# HILOW_Drivers.net
KiCad netlist of a schematic drawn in EasyEDA Pro
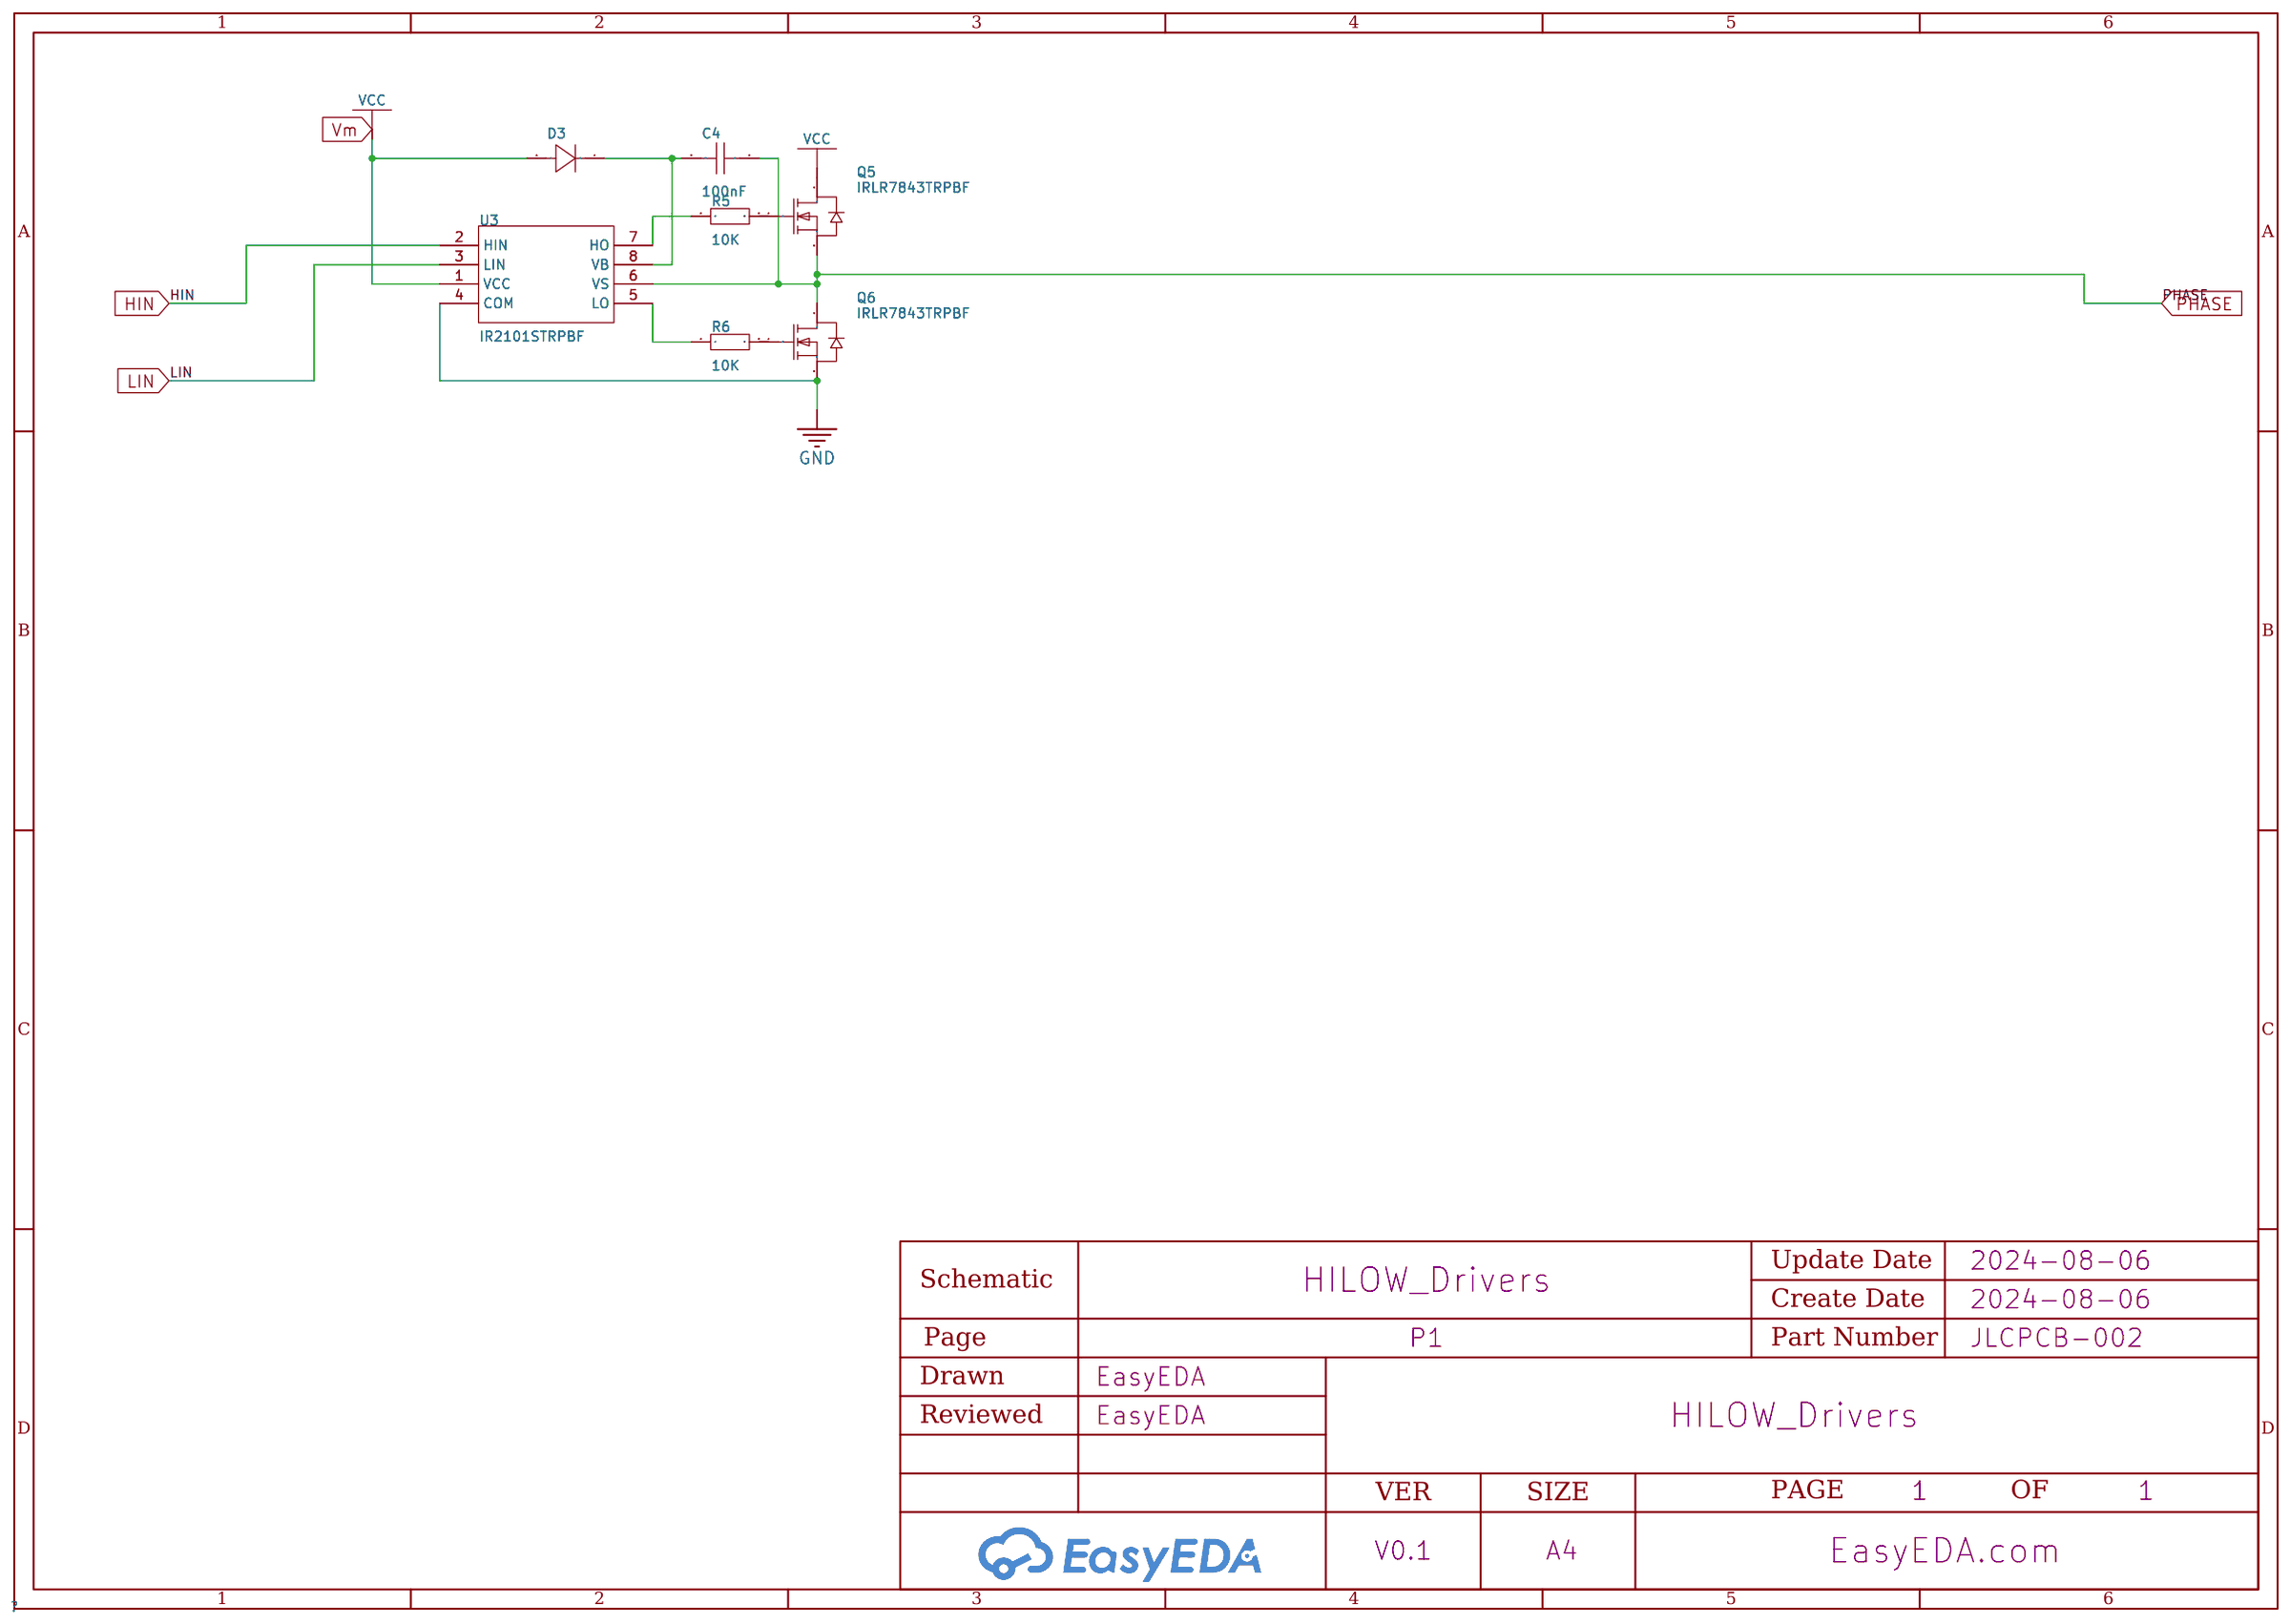
[diagram p0: schematic sheet]

(export (version "E")
  (design (tool "Eeschema 10.0.6"))
  (components
    (comp (ref "C4")
      (value "100nF")
      (footprint "easyedapro:C0603")
      (libsource (lib "easyedapro") (part "CAP"))
    )
    (comp (ref "D3")
      (value "~")
      (footprint "easyedapro:DO-41_BD2.4-L4.7-P8.70-D0.9-RD")
      (libsource (lib "easyedapro") (part "D_1N4007"))
    )
    (comp (ref "Q5")
      (value "IRLR7843TRPBF")
      (footprint "easyedapro:TO-252-2_L6.5-W6.1-P4.58-LS10.0-TR")
      (fields (field (name "Manufacturer") "Infineon(英飞凌)"))
      (libsource (lib "easyedapro") (part "IRLR7843TRPBF"))
    )
    (comp (ref "Q6")
      (value "IRLR7843TRPBF")
      (footprint "easyedapro:TO-252-2_L6.5-W6.1-P4.58-LS10.0-TR")
      (fields (field (name "Manufacturer") "Infineon(英飞凌)"))
      (libsource (lib "easyedapro") (part "IRLR7843TRPBF"))
    )
    (comp (ref "R5") (value "10K") (footprint "easyedapro:R0603") (libsource (lib "easyedapro") (part "Res")))
    (comp (ref "R6") (value "10K") (footprint "easyedapro:R0603") (libsource (lib "easyedapro") (part "Res")))
    (comp (ref "U3")
      (value "IR2101STRPBF")
      (footprint "easyedapro:SOIC-8_L5.0-W4.0-P1.27-LS6.0-BL")
      (fields (field (name "Manufacturer") "Infineon(英飞凌)"))
      (libsource (lib "easyedapro") (part "IR2101STRPBF"))
    )
  )
  (nets
    (net (code "1") (name "GND") (class "Default")
      (node (ref "Q6") (pin "3") (pinfunction "S_3") (pintype "unspecified"))
      (node (ref "U3") (pin "4") (pinfunction "COM_4") (pintype "unspecified"))
    )
    (net (code "2") (name "HIN") (class "Default")
      (node (ref "U3") (pin "2") (pinfunction "HIN_2") (pintype "unspecified"))
    )
    (net (code "3") (name "LIN") (class "Default")
      (node (ref "U3") (pin "3") (pinfunction "LIN_3") (pintype "unspecified"))
    )
    (net (code "4") (name "Net-(D3-K)") (class "Default")
      (node (ref "C4") (pin "2") (pinfunction "2_2") (pintype "input"))
      (node (ref "D3") (pin "1") (pinfunction "K_1") (pintype "input"))
      (node (ref "U3") (pin "8") (pinfunction "VB_8") (pintype "unspecified"))
    )
    (net (code "5") (name "Net-(Q5-G)") (class "Default")
      (node (ref "Q5") (pin "1") (pinfunction "G_1") (pintype "unspecified"))
      (node (ref "R5") (pin "2") (pinfunction "2_2") (pintype "input"))
    )
    (net (code "6") (name "Net-(Q6-G)") (class "Default")
      (node (ref "Q6") (pin "1") (pinfunction "G_1") (pintype "unspecified"))
      (node (ref "R6") (pin "2") (pinfunction "2_2") (pintype "input"))
    )
    (net (code "7") (name "Net-(U3-HO)") (class "Default")
      (node (ref "R5") (pin "1") (pinfunction "1_1") (pintype "input"))
      (node (ref "U3") (pin "7") (pinfunction "HO_7") (pintype "output"))
    )
    (net (code "8") (name "Net-(U3-LO)") (class "Default")
      (node (ref "R6") (pin "1") (pinfunction "1_1") (pintype "input"))
      (node (ref "U3") (pin "5") (pinfunction "LO_5") (pintype "output"))
    )
    (net (code "9") (name "PHASE") (class "Default")
      (node (ref "C4") (pin "1") (pinfunction "1_1") (pintype "input"))
      (node (ref "Q5") (pin "3") (pinfunction "S_3") (pintype "unspecified"))
      (node (ref "Q6") (pin "4") (pinfunction "D_4") (pintype "unspecified"))
      (node (ref "U3") (pin "6") (pinfunction "VS_6") (pintype "unspecified"))
    )
    (net (code "10") (name "VCC") (class "Default")
      (node (ref "D3") (pin "2") (pinfunction "A_2") (pintype "input"))
      (node (ref "Q5") (pin "4") (pinfunction "D_4") (pintype "unspecified"))
      (node (ref "U3") (pin "1") (pinfunction "VCC_1") (pintype "unspecified"))
    )
  )
)
